# SCH_555-Circuit_2025-11-01.net
KiCad netlist of a schematic drawn in EasyEDA
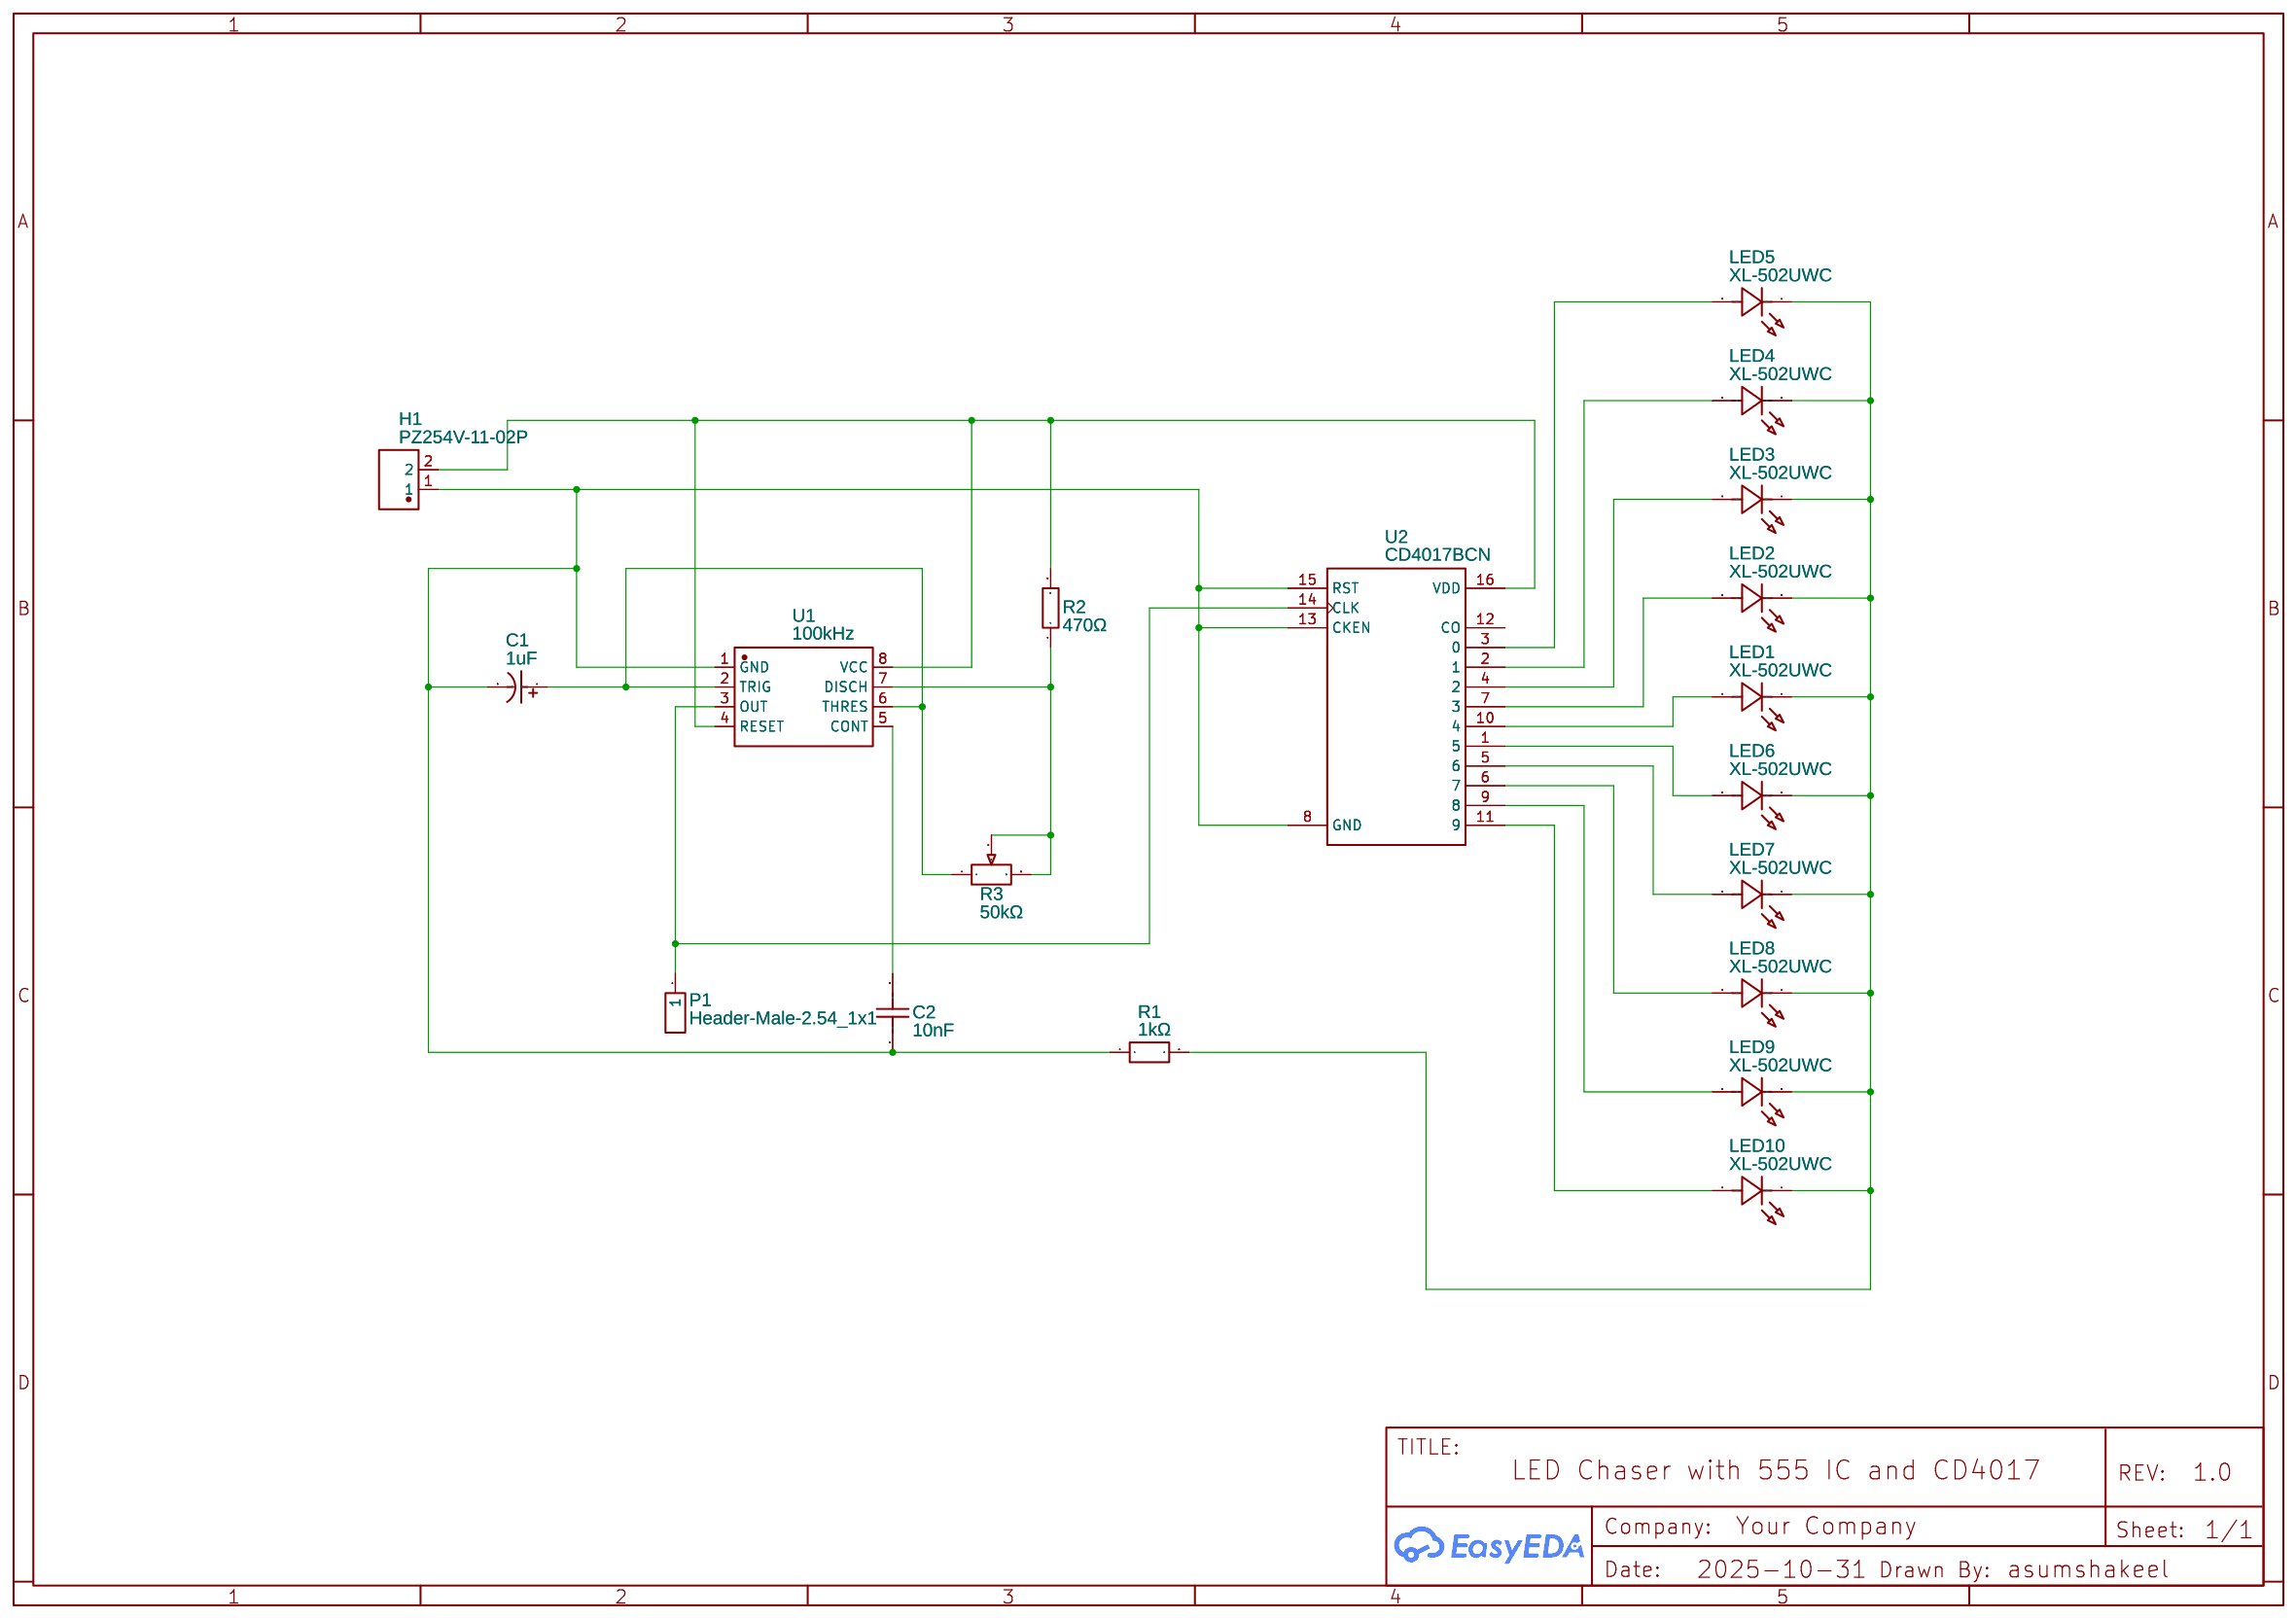
[diagram p0: schematic sheet]

(export (version "E")
  (design (tool "Eeschema 10.0.6"))
  (components
    (comp (ref "C1")
      (value "1uF")
      (fields (field (name "Manufacturer Part") "KF010M050C110A") (field (name "Manufacturer") "CapXon(丰宾)"))
      (libsource (lib "") (part "KF010M050C110A"))
    )
    (comp (ref "C2")
      (value "10nF")
      (fields (field (name "Manufacturer Part") "N09F1B103MN0B0S0N0") (field (name "Manufacturer") "STE(松田)"))
      (libsource (lib "") (part "N09F1B103MN0B0S0N0"))
    )
    (comp (ref "H1")
      (value "PZ254V-11-02P")
      (fields (field (name "Manufacturer") "XFCN(兴飞)"))
      (libsource (lib "") (part "PZ254V-11-02P"))
    )
    (comp (ref "LED1")
      (value "XL-502UWC")
      (fields (field (name "Manufacturer") "XINGLIGHT(成兴光)"))
      (libsource (lib "") (part "XL-502UWC"))
    )
    (comp (ref "LED2")
      (value "XL-502UWC")
      (fields (field (name "Manufacturer") "XINGLIGHT(成兴光)"))
      (libsource (lib "") (part "XL-502UWC"))
    )
    (comp (ref "LED3")
      (value "XL-502UWC")
      (fields (field (name "Manufacturer") "XINGLIGHT(成兴光)"))
      (libsource (lib "") (part "XL-502UWC"))
    )
    (comp (ref "LED4")
      (value "XL-502UWC")
      (fields (field (name "Manufacturer") "XINGLIGHT(成兴光)"))
      (libsource (lib "") (part "XL-502UWC"))
    )
    (comp (ref "LED5")
      (value "XL-502UWC")
      (fields (field (name "Manufacturer") "XINGLIGHT(成兴光)"))
      (libsource (lib "") (part "XL-502UWC"))
    )
    (comp (ref "LED6")
      (value "XL-502UWC")
      (fields (field (name "Manufacturer") "XINGLIGHT(成兴光)"))
      (libsource (lib "") (part "XL-502UWC"))
    )
    (comp (ref "LED7")
      (value "XL-502UWC")
      (fields (field (name "Manufacturer") "XINGLIGHT(成兴光)"))
      (libsource (lib "") (part "XL-502UWC"))
    )
    (comp (ref "LED8")
      (value "XL-502UWC")
      (fields (field (name "Manufacturer") "XINGLIGHT(成兴光)"))
      (libsource (lib "") (part "XL-502UWC"))
    )
    (comp (ref "LED9")
      (value "XL-502UWC")
      (fields (field (name "Manufacturer") "XINGLIGHT(成兴光)"))
      (libsource (lib "") (part "XL-502UWC"))
    )
    (comp (ref "LED10")
      (value "XL-502UWC")
      (fields (field (name "Manufacturer") "XINGLIGHT(成兴光)"))
      (libsource (lib "") (part "XL-502UWC"))
    )
    (comp (ref "P1")
      (value "Header-Male-2.54_1x1")
      (fields (field (name "Manufacturer Part") "2.54-1*1P针") (field (name "Manufacturer") "BOOMELE(博穆精密)"))
      (libsource (lib "") (part "Header-Male-2.54_1x1"))
    )
    (comp (ref "R1")
      (value "1kΩ")
      (fields (field (name "Manufacturer Part") "MF1/4W-1KΩ±1%T52") (field (name "Manufacturer") "华星机电"))
      (libsource (lib "") (part "MF1/4W-1KΩ±1%T52"))
    )
    (comp (ref "R2")
      (value "470Ω")
      (fields
        (field (name "Manufacturer Part") "MFR0W4F4700A50")
        (field (name "Manufacturer") "UNI-ROYAL(厚声)")
      )
      (libsource (lib "") (part "MFR0W4F4700A50"))
    )
    (comp (ref "R3")
      (value "50kΩ")
      (fields (field (name "Manufacturer Part") "3296X-1-503") (field (name "Manufacturer") "BOCHEN(博晨)"))
      (libsource (lib "") (part "3296X-1-503_C118912"))
    )
    (comp (ref "U1")
      (value "100kHz")
      (fields (field (name "Manufacturer Part") "NE555P") (field (name "Manufacturer") "TI(德州仪器)"))
      (libsource (lib "") (part "NE555P"))
    )
    (comp (ref "U2") (value "CD4017BCN") (libsource (lib "") (part "CD4017BCN")))
  )
  (nets
    (net (code "1") (name "Net-(LED1-A)") (class "Default")
      (node (ref "LED1") (pin "2") (pinfunction "A_2") (pintype "unspecified"))
      (node (ref "U2") (pin "10") (pinfunction "4_10") (pintype "output"))
    )
    (net (code "2") (name "Net-(LED1-K)") (class "Default")
      (node (ref "LED1") (pin "1") (pinfunction "K_1") (pintype "unspecified"))
      (node (ref "LED10") (pin "1") (pinfunction "K_1") (pintype "unspecified"))
      (node (ref "LED2") (pin "1") (pinfunction "K_1") (pintype "unspecified"))
      (node (ref "LED3") (pin "1") (pinfunction "K_1") (pintype "unspecified"))
      (node (ref "LED4") (pin "1") (pinfunction "K_1") (pintype "unspecified"))
      (node (ref "LED5") (pin "1") (pinfunction "K_1") (pintype "unspecified"))
      (node (ref "LED6") (pin "1") (pinfunction "K_1") (pintype "unspecified"))
      (node (ref "LED7") (pin "1") (pinfunction "K_1") (pintype "unspecified"))
      (node (ref "LED8") (pin "1") (pinfunction "K_1") (pintype "unspecified"))
      (node (ref "LED9") (pin "1") (pinfunction "K_1") (pintype "unspecified"))
      (node (ref "R1") (pin "2") (pinfunction "2_2") (pintype "unspecified"))
    )
    (net (code "3") (name "Net-(LED2-A)") (class "Default")
      (node (ref "LED2") (pin "2") (pinfunction "A_2") (pintype "unspecified"))
      (node (ref "U2") (pin "7") (pinfunction "3_7") (pintype "output"))
    )
    (net (code "4") (name "Net-(LED3-A)") (class "Default")
      (node (ref "LED3") (pin "2") (pinfunction "A_2") (pintype "unspecified"))
      (node (ref "U2") (pin "4") (pinfunction "2_4") (pintype "output"))
    )
    (net (code "5") (name "Net-(LED4-A)") (class "Default")
      (node (ref "LED4") (pin "2") (pinfunction "A_2") (pintype "unspecified"))
      (node (ref "U2") (pin "2") (pinfunction "1_2") (pintype "output"))
    )
    (net (code "6") (name "Net-(LED5-A)") (class "Default")
      (node (ref "LED5") (pin "2") (pinfunction "A_2") (pintype "unspecified"))
      (node (ref "U2") (pin "3") (pinfunction "0_3") (pintype "output"))
    )
    (net (code "7") (name "Net-(LED6-A)") (class "Default")
      (node (ref "LED6") (pin "2") (pinfunction "A_2") (pintype "unspecified"))
      (node (ref "U2") (pin "1") (pinfunction "5_1") (pintype "output"))
    )
    (net (code "8") (name "Net-(LED7-A)") (class "Default")
      (node (ref "LED7") (pin "2") (pinfunction "A_2") (pintype "unspecified"))
      (node (ref "U2") (pin "5") (pinfunction "6_5") (pintype "output"))
    )
    (net (code "9") (name "Net-(LED8-A)") (class "Default")
      (node (ref "LED8") (pin "2") (pinfunction "A_2") (pintype "unspecified"))
      (node (ref "U2") (pin "6") (pinfunction "7_6") (pintype "output"))
    )
    (net (code "10") (name "Net-(LED9-A)") (class "Default")
      (node (ref "LED9") (pin "2") (pinfunction "A_2") (pintype "unspecified"))
      (node (ref "U2") (pin "9") (pinfunction "8_9") (pintype "output"))
    )
    (net (code "11") (name "Net-(LED10-A)") (class "Default")
      (node (ref "LED10") (pin "2") (pinfunction "A_2") (pintype "unspecified"))
      (node (ref "U2") (pin "11") (pinfunction "9_11") (pintype "output"))
    )
    (net (code "12") (name "Net-(U1-CONT)") (class "Default")
      (node (ref "C2") (pin "2") (pinfunction "2_2") (pintype "unspecified"))
      (node (ref "U1") (pin "5") (pinfunction "CONT_5") (pintype "unspecified"))
    )
    (net (code "13") (name "Net-(U1-DISCH)") (class "Default")
      (node (ref "R2") (pin "1") (pinfunction "1_1") (pintype "input"))
      (node (ref "R3") (pin "2") (pinfunction "2_2") (pintype "input"))
      (node (ref "R3") (pin "3") (pinfunction "3_3") (pintype "input"))
      (node (ref "U1") (pin "7") (pinfunction "DISCH_7") (pintype "unspecified"))
    )
    (net (code "14") (name "Net-(U1-GND)") (class "Default")
      (node (ref "C1") (pin "2") (pinfunction "2_2") (pintype "input"))
      (node (ref "C2") (pin "1") (pinfunction "1_1") (pintype "unspecified"))
      (node (ref "H1") (pin "1") (pinfunction "1_1") (pintype "unspecified"))
      (node (ref "R1") (pin "1") (pinfunction "1_1") (pintype "unspecified"))
      (node (ref "U1") (pin "1") (pinfunction "GND_1") (pintype "unspecified"))
      (node (ref "U2") (pin "13") (pinfunction "CKEN_13") (pintype "unspecified"))
      (node (ref "U2") (pin "15") (pinfunction "RST_15") (pintype "unspecified"))
      (node (ref "U2") (pin "8") (pinfunction "GND_8") (pintype "passive"))
    )
    (net (code "15") (name "Net-(U1-OUT)") (class "Default")
      (node (ref "P1") (pin "1") (pinfunction "1_1") (pintype "input"))
      (node (ref "U1") (pin "3") (pinfunction "OUT_3") (pintype "unspecified"))
      (node (ref "U2") (pin "14") (pinfunction "CLK_14") (pintype "unspecified"))
    )
    (net (code "16") (name "Net-(U1-RESET)") (class "Default")
      (node (ref "H1") (pin "2") (pinfunction "2_2") (pintype "unspecified"))
      (node (ref "R2") (pin "2") (pinfunction "2_2") (pintype "input"))
      (node (ref "U1") (pin "4") (pinfunction "RESET_4") (pintype "unspecified"))
      (node (ref "U1") (pin "8") (pinfunction "VCC_8") (pintype "unspecified"))
      (node (ref "U2") (pin "16") (pinfunction "VDD_16") (pintype "passive"))
    )
    (net (code "17") (name "Net-(U1-THRES)") (class "Default")
      (node (ref "C1") (pin "1") (pinfunction "1_1") (pintype "input"))
      (node (ref "R3") (pin "1") (pinfunction "1_1") (pintype "input"))
      (node (ref "U1") (pin "2") (pinfunction "TRIG_2") (pintype "unspecified"))
      (node (ref "U1") (pin "6") (pinfunction "THRES_6") (pintype "unspecified"))
    )
    (net (code "18") (name "unconnected-(U2-CO-Pad12)") (class "Default")
      (node (ref "U2") (pin "12") (pinfunction "CO_12") (pintype "output"))
    )
  )
)
